# main_schematic.net
KiCad netlist of a schematic drawn in EAGLE
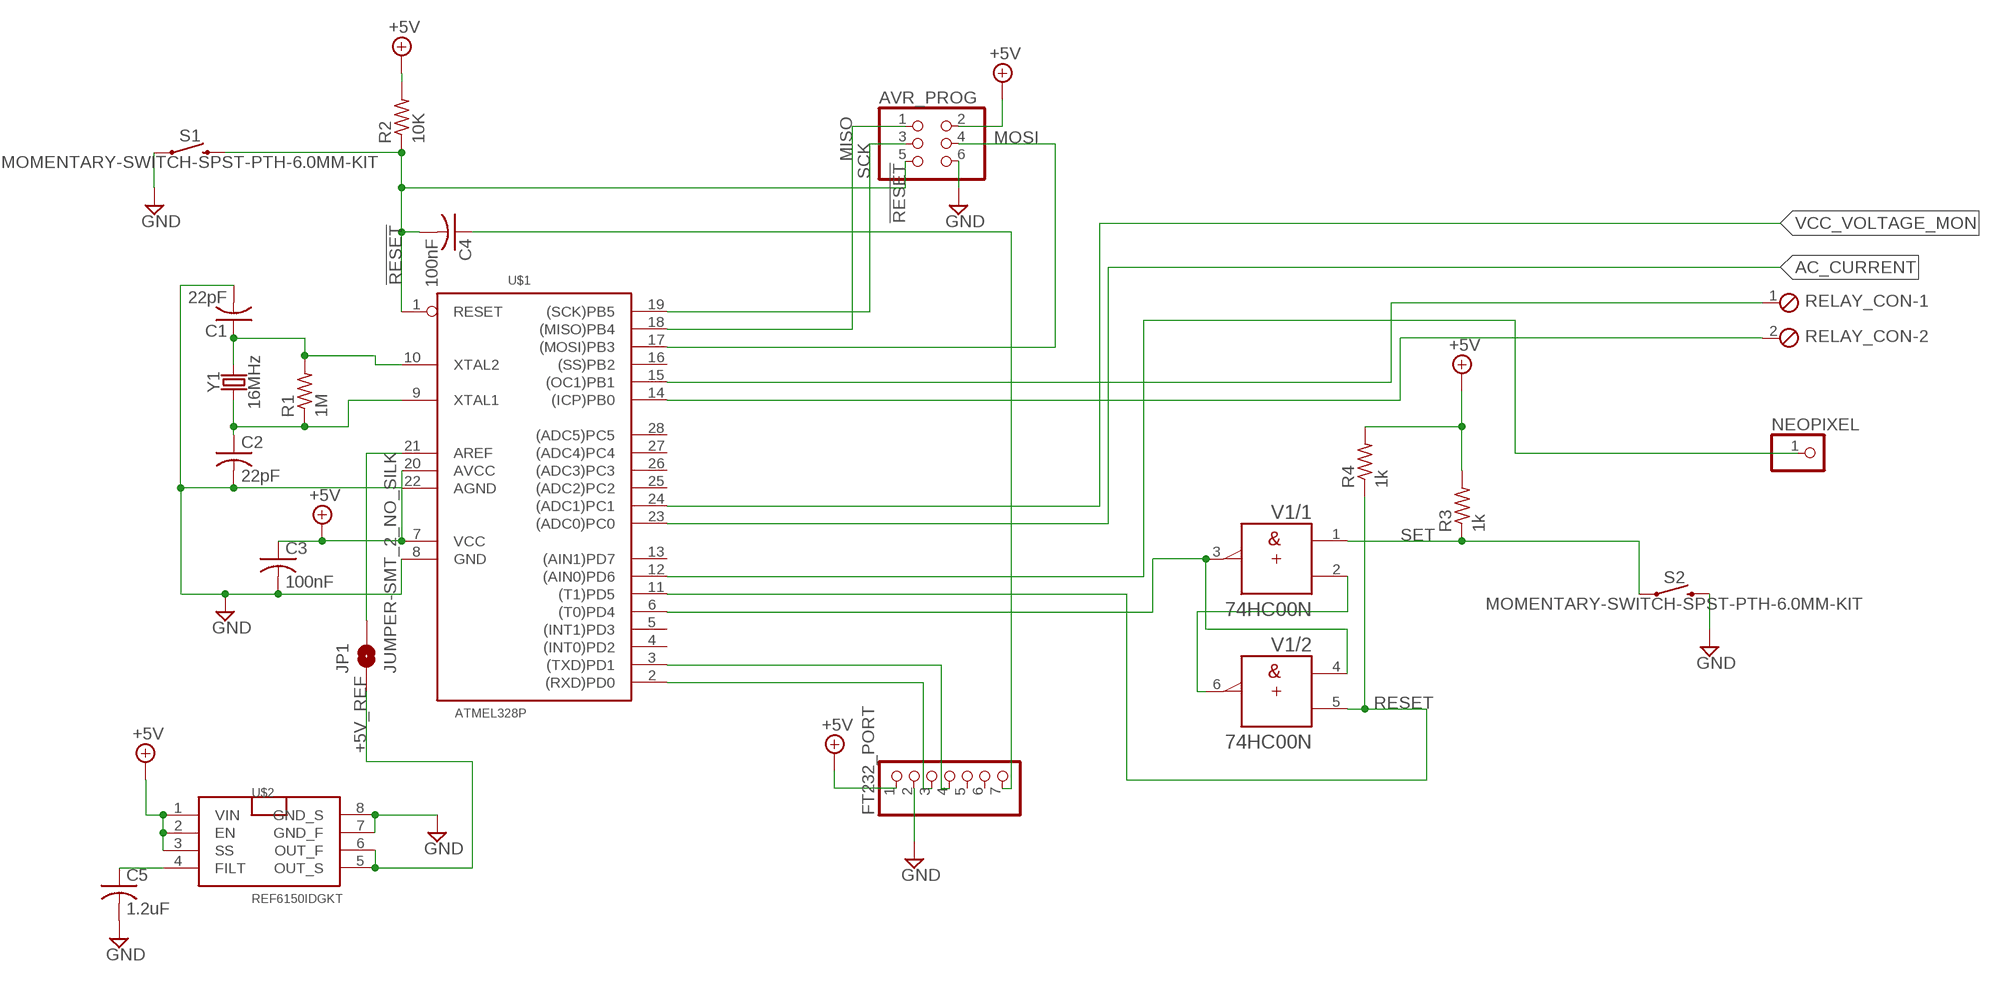
[diagram p0: schematic, sheet 1]

(export (version "E")
  (design (tool "Eeschema 10.0.6"))
  (components
    (comp (ref "AVR_PROG")
      (value "PINHD-2X3")
      (footprint "eagle-import:2X03")
      (libsource (lib "eagle-import") (part "PINHD-2X3"))
    )
    (comp (ref "C1")
      (value "22pF")
      (footprint "eagle-import:C1206")
      (libsource (lib "eagle-import") (part "C-USC1206"))
    )
    (comp (ref "C2")
      (value "22pF")
      (footprint "eagle-import:C1206")
      (libsource (lib "eagle-import") (part "C-USC1206"))
    )
    (comp (ref "C3")
      (value "100nF")
      (footprint "eagle-import:C1206")
      (libsource (lib "eagle-import") (part "C-USC1206"))
    )
    (comp (ref "C4")
      (value "100nF")
      (footprint "eagle-import:C1206")
      (libsource (lib "eagle-import") (part "C-USC1206"))
    )
    (comp (ref "C5")
      (value "1.2uF")
      (footprint "eagle-import:C1206")
      (libsource (lib "eagle-import") (part "C-USC1206"))
    )
    (comp (ref "FT232_PORT")
      (value "PINHD-1X7")
      (footprint "eagle-import:1X07")
      (libsource (lib "eagle-import") (part "PINHD-1X7"))
    )
    (comp (ref "JP1")
      (value "JUMPER-SMT_2_NO_SILK")
      (footprint "eagle-import:SMT-JUMPER_2_NO_SILK")
      (libsource (lib "eagle-import") (part "JUMPER-SMT_2_NO_SILK"))
    )
    (comp (ref "NEOPIXEL")
      (value "PINHD-1X1")
      (footprint "eagle-import:1X01")
      (libsource (lib "eagle-import") (part "PINHD-1X1"))
    )
    (comp (ref "R1")
      (value "1M")
      (footprint "eagle-import:0309_10")
      (libsource (lib "eagle-import") (part "R-US_0309/10"))
    )
    (comp (ref "R2")
      (value "10K")
      (footprint "eagle-import:0309_10")
      (libsource (lib "eagle-import") (part "R-US_0309/10"))
    )
    (comp (ref "R3")
      (value "1k")
      (footprint "eagle-import:0309_10")
      (libsource (lib "eagle-import") (part "R-US_0309/10"))
    )
    (comp (ref "R4")
      (value "1k")
      (footprint "eagle-import:0309_10")
      (libsource (lib "eagle-import") (part "R-US_0309/10"))
    )
    (comp (ref "RELAY_CON")
      (value "MPT2")
      (footprint "eagle-import:2POL254")
      (libsource (lib "eagle-import") (part "MPT2"))
    )
    (comp (ref "S1")
      (value "MOMENTARY-SWITCH-SPST-PTH-6.0MM-KIT")
      (footprint "eagle-import:TACTILE_SWITCH_PTH_6.0MM_KIT")
      (libsource (lib "eagle-import") (part "MOMENTARY-SWITCH-SPST-PTH-6.0MM-KIT"))
    )
    (comp (ref "S2")
      (value "MOMENTARY-SWITCH-SPST-PTH-6.0MM-KIT")
      (footprint "eagle-import:TACTILE_SWITCH_PTH_6.0MM_KIT")
      (libsource (lib "eagle-import") (part "MOMENTARY-SWITCH-SPST-PTH-6.0MM-KIT"))
    )
    (comp (ref "U$1")
      (value "ATMEL328P")
      (footprint "eagle-import:DIL28-3")
      (libsource (lib "eagle-import") (part "ATMEL328P"))
    )
    (comp (ref "U$2")
      (value "REF6150IDGKT")
      (footprint "eagle-import:TSSOP8")
      (libsource (lib "eagle-import") (part "REF6150IDGKT"))
    )
    (comp (ref "V1")
      (value "74HC00N")
      (footprint "eagle-import:DIL14")
      (libsource (lib "eagle-import") (part "7400NHC"))
    )
    (comp (ref "Y1")
      (value "16MHz")
      (footprint "eagle-import:HC49US")
      (libsource (lib "eagle-import") (part "CRYSTAL-16MHZPTH-HC49US"))
    )
  )
  (nets
    (net (code "1") (name "+5V") (class "Default")
      (node (ref "AVR_PROG") (pin "2") (pinfunction "2_2") (pintype "passive"))
      (node (ref "C3") (pin "1") (pinfunction "1_1") (pintype "passive"))
      (node (ref "FT232_PORT") (pin "1") (pinfunction "1_1") (pintype "passive"))
      (node (ref "R2") (pin "2") (pinfunction "2_2") (pintype "passive"))
      (node (ref "R3") (pin "2") (pinfunction "2_2") (pintype "passive"))
      (node (ref "R4") (pin "2") (pinfunction "2_2") (pintype "passive"))
      (node (ref "U$1") (pin "20") (pinfunction "AVCC_20") (pintype "bidirectional"))
      (node (ref "U$1") (pin "7") (pinfunction "VCC_7") (pintype "bidirectional"))
      (node (ref "U$2") (pin "1") (pinfunction "VIN_1") (pintype "bidirectional"))
      (node (ref "U$2") (pin "2") (pinfunction "EN_2") (pintype "bidirectional"))
      (node (ref "U$2") (pin "3") (pinfunction "SS_3") (pintype "bidirectional"))
    )
    (net (code "2") (name "/+5V_REF") (class "Default")
      (node (ref "JP1") (pin "1") (pinfunction "1_1") (pintype "passive"))
      (node (ref "U$2") (pin "5") (pinfunction "OUT_S_5") (pintype "bidirectional"))
      (node (ref "U$2") (pin "6") (pinfunction "OUT_F_6") (pintype "bidirectional"))
    )
    (net (code "3") (name "/MISO") (class "Default")
      (node (ref "AVR_PROG") (pin "1") (pinfunction "1_1") (pintype "passive"))
      (node (ref "U$1") (pin "18") (pinfunction "(MISO)PB4_18") (pintype "bidirectional"))
    )
    (net (code "4") (name "/MOSI") (class "Default")
      (node (ref "AVR_PROG") (pin "4") (pinfunction "4_4") (pintype "passive"))
      (node (ref "U$1") (pin "17") (pinfunction "(MOSI)PB3_17") (pintype "bidirectional"))
    )
    (net (code "5") (name "/RESET") (class "Default")
      (node (ref "R4") (pin "1") (pinfunction "1_1") (pintype "passive"))
      (node (ref "U$1") (pin "11") (pinfunction "(T1)PD5_11") (pintype "bidirectional"))
      (node (ref "V1") (pin "5") (pinfunction "B_5") (pintype "input"))
    )
    (net (code "6") (name "/SCK") (class "Default")
      (node (ref "AVR_PROG") (pin "3") (pinfunction "3_3") (pintype "passive"))
      (node (ref "U$1") (pin "19") (pinfunction "(SCK)PB5_19") (pintype "bidirectional"))
    )
    (net (code "7") (name "/SET") (class "Default")
      (node (ref "R3") (pin "1") (pinfunction "1_1") (pintype "passive"))
      (node (ref "S2") (pin "1") (pinfunction "1_1") (pintype "passive"))
      (node (ref "V1") (pin "1") (pinfunction "A_1") (pintype "input"))
    )
    (net (code "8") (name "/~{RESET}") (class "Default")
      (node (ref "AVR_PROG") (pin "5") (pinfunction "5_5") (pintype "passive"))
      (node (ref "C4") (pin "2") (pinfunction "2_2") (pintype "passive"))
      (node (ref "R2") (pin "1") (pinfunction "1_1") (pintype "passive"))
      (node (ref "S1") (pin "3") (pinfunction "2_3") (pintype "passive"))
      (node (ref "U$1") (pin "1") (pinfunction "RESET_1") (pintype "bidirectional"))
    )
    (net (code "9") (name "AC_CURRENT") (class "Default")
      (node (ref "U$1") (pin "23") (pinfunction "(ADC0)PC0_23") (pintype "bidirectional"))
    )
    (net (code "10") (name "GND") (class "Default")
      (node (ref "AVR_PROG") (pin "6") (pinfunction "6_6") (pintype "passive"))
      (node (ref "C1") (pin "2") (pinfunction "2_2") (pintype "passive"))
      (node (ref "C2") (pin "2") (pinfunction "2_2") (pintype "passive"))
      (node (ref "C3") (pin "2") (pinfunction "2_2") (pintype "passive"))
      (node (ref "C5") (pin "2") (pinfunction "2_2") (pintype "passive"))
      (node (ref "FT232_PORT") (pin "2") (pinfunction "2_2") (pintype "passive"))
      (node (ref "S1") (pin "1") (pinfunction "1_1") (pintype "passive"))
      (node (ref "S2") (pin "3") (pinfunction "2_3") (pintype "passive"))
      (node (ref "U$1") (pin "22") (pinfunction "AGND_22") (pintype "bidirectional"))
      (node (ref "U$1") (pin "8") (pinfunction "GND_8") (pintype "bidirectional"))
      (node (ref "U$2") (pin "7") (pinfunction "GND_F_7") (pintype "bidirectional"))
      (node (ref "U$2") (pin "8") (pinfunction "GND_S_8") (pintype "bidirectional"))
    )
    (net (code "11") (name "Net-(C4-Pad1)") (class "Default")
      (node (ref "C4") (pin "1") (pinfunction "1_1") (pintype "passive"))
      (node (ref "FT232_PORT") (pin "7") (pinfunction "7_7") (pintype "passive"))
    )
    (net (code "12") (name "Net-(RELAY_CONB-1)") (class "Default")
      (node (ref "RELAY_CON") (pin "2") (pinfunction "1_2") (pintype "passive"))
      (node (ref "U$1") (pin "14") (pinfunction "(ICP)PB0_14") (pintype "bidirectional"))
    )
    (net (code "13") (name "Net-(U$1-(AIN0)PD6)") (class "Default")
      (node (ref "NEOPIXEL") (pin "1") (pinfunction "1_1") (pintype "passive"))
      (node (ref "U$1") (pin "12") (pinfunction "(AIN0)PD6_12") (pintype "bidirectional"))
    )
    (net (code "14") (name "Net-(U$1-(OC1)PB1)") (class "Default")
      (node (ref "RELAY_CON") (pin "1") (pinfunction "1_1") (pintype "passive"))
      (node (ref "U$1") (pin "15") (pinfunction "(OC1)PB1_15") (pintype "bidirectional"))
    )
    (net (code "15") (name "Net-(U$1-(RXD)PD0)") (class "Default")
      (node (ref "FT232_PORT") (pin "3") (pinfunction "3_3") (pintype "passive"))
      (node (ref "U$1") (pin "2") (pinfunction "(RXD)PD0_2") (pintype "bidirectional"))
    )
    (net (code "16") (name "Net-(U$1-(T0)PD4)") (class "Default")
      (node (ref "U$1") (pin "6") (pinfunction "(T0)PD4_6") (pintype "bidirectional"))
      (node (ref "V1") (pin "3") (pinfunction "Y_3") (pintype "output"))
      (node (ref "V1") (pin "4") (pinfunction "A_4") (pintype "input"))
    )
    (net (code "17") (name "Net-(U$1-(TXD)PD1)") (class "Default")
      (node (ref "FT232_PORT") (pin "4") (pinfunction "4_4") (pintype "passive"))
      (node (ref "U$1") (pin "3") (pinfunction "(TXD)PD1_3") (pintype "bidirectional"))
    )
    (net (code "18") (name "Net-(U$1-AREF)") (class "Default")
      (node (ref "JP1") (pin "2") (pinfunction "2_2") (pintype "passive"))
      (node (ref "U$1") (pin "21") (pinfunction "AREF_21") (pintype "bidirectional"))
    )
    (net (code "19") (name "Net-(U$1-XTAL1)") (class "Default")
      (node (ref "C2") (pin "1") (pinfunction "1_1") (pintype "passive"))
      (node (ref "R1") (pin "1") (pinfunction "1_1") (pintype "passive"))
      (node (ref "U$1") (pin "9") (pinfunction "XTAL1_9") (pintype "bidirectional"))
      (node (ref "Y1") (pin "1") (pinfunction "1_1") (pintype "passive"))
    )
    (net (code "20") (name "Net-(U$1-XTAL2)") (class "Default")
      (node (ref "C1") (pin "1") (pinfunction "1_1") (pintype "passive"))
      (node (ref "R1") (pin "2") (pinfunction "2_2") (pintype "passive"))
      (node (ref "U$1") (pin "10") (pinfunction "XTAL2_10") (pintype "bidirectional"))
      (node (ref "Y1") (pin "2") (pinfunction "2_2") (pintype "passive"))
    )
    (net (code "21") (name "Net-(U$2-FILT)") (class "Default")
      (node (ref "C5") (pin "1") (pinfunction "1_1") (pintype "passive"))
      (node (ref "U$2") (pin "4") (pinfunction "FILT_4") (pintype "bidirectional"))
    )
    (net (code "22") (name "Net-(V1C-B)") (class "Default")
      (node (ref "V1") (pin "2") (pinfunction "B_2") (pintype "input"))
      (node (ref "V1") (pin "6") (pinfunction "Y_6") (pintype "output"))
    )
    (net (code "23") (name "VCC_VOLTAGE_MON") (class "Default")
      (node (ref "U$1") (pin "24") (pinfunction "(ADC1)PC1_24") (pintype "bidirectional"))
    )
    (net (code "24") (name "unconnected-(FT232_PORT-Pad5)") (class "Default")
      (node (ref "FT232_PORT") (pin "5") (pinfunction "5_5") (pintype "passive"))
    )
    (net (code "25") (name "unconnected-(FT232_PORT-Pad6)") (class "Default")
      (node (ref "FT232_PORT") (pin "6") (pinfunction "6_6") (pintype "passive"))
    )
    (net (code "26") (name "unconnected-(U$1-(ADC2)PC2-Pad25)") (class "Default")
      (node (ref "U$1") (pin "25") (pinfunction "(ADC2)PC2_25") (pintype "bidirectional"))
    )
    (net (code "27") (name "unconnected-(U$1-(ADC3)PC3-Pad26)") (class "Default")
      (node (ref "U$1") (pin "26") (pinfunction "(ADC3)PC3_26") (pintype "bidirectional"))
    )
    (net (code "28") (name "unconnected-(U$1-(ADC4)PC4-Pad27)") (class "Default")
      (node (ref "U$1") (pin "27") (pinfunction "(ADC4)PC4_27") (pintype "bidirectional"))
    )
    (net (code "29") (name "unconnected-(U$1-(ADC5)PC5-Pad28)") (class "Default")
      (node (ref "U$1") (pin "28") (pinfunction "(ADC5)PC5_28") (pintype "bidirectional"))
    )
    (net (code "30") (name "unconnected-(U$1-(AIN1)PD7-Pad13)") (class "Default")
      (node (ref "U$1") (pin "13") (pinfunction "(AIN1)PD7_13") (pintype "bidirectional"))
    )
    (net (code "31") (name "unconnected-(U$1-(INT0)PD2-Pad4)") (class "Default")
      (node (ref "U$1") (pin "4") (pinfunction "(INT0)PD2_4") (pintype "bidirectional"))
    )
    (net (code "32") (name "unconnected-(U$1-(INT1)PD3-Pad5)") (class "Default")
      (node (ref "U$1") (pin "5") (pinfunction "(INT1)PD3_5") (pintype "bidirectional"))
    )
    (net (code "33") (name "unconnected-(U$1-(SS)PB2-Pad16)") (class "Default")
      (node (ref "U$1") (pin "16") (pinfunction "(SS)PB2_16") (pintype "bidirectional"))
    )
  )
)
